# Soldering_Tip.net
KiCad netlist of a schematic drawn in Altium Designer
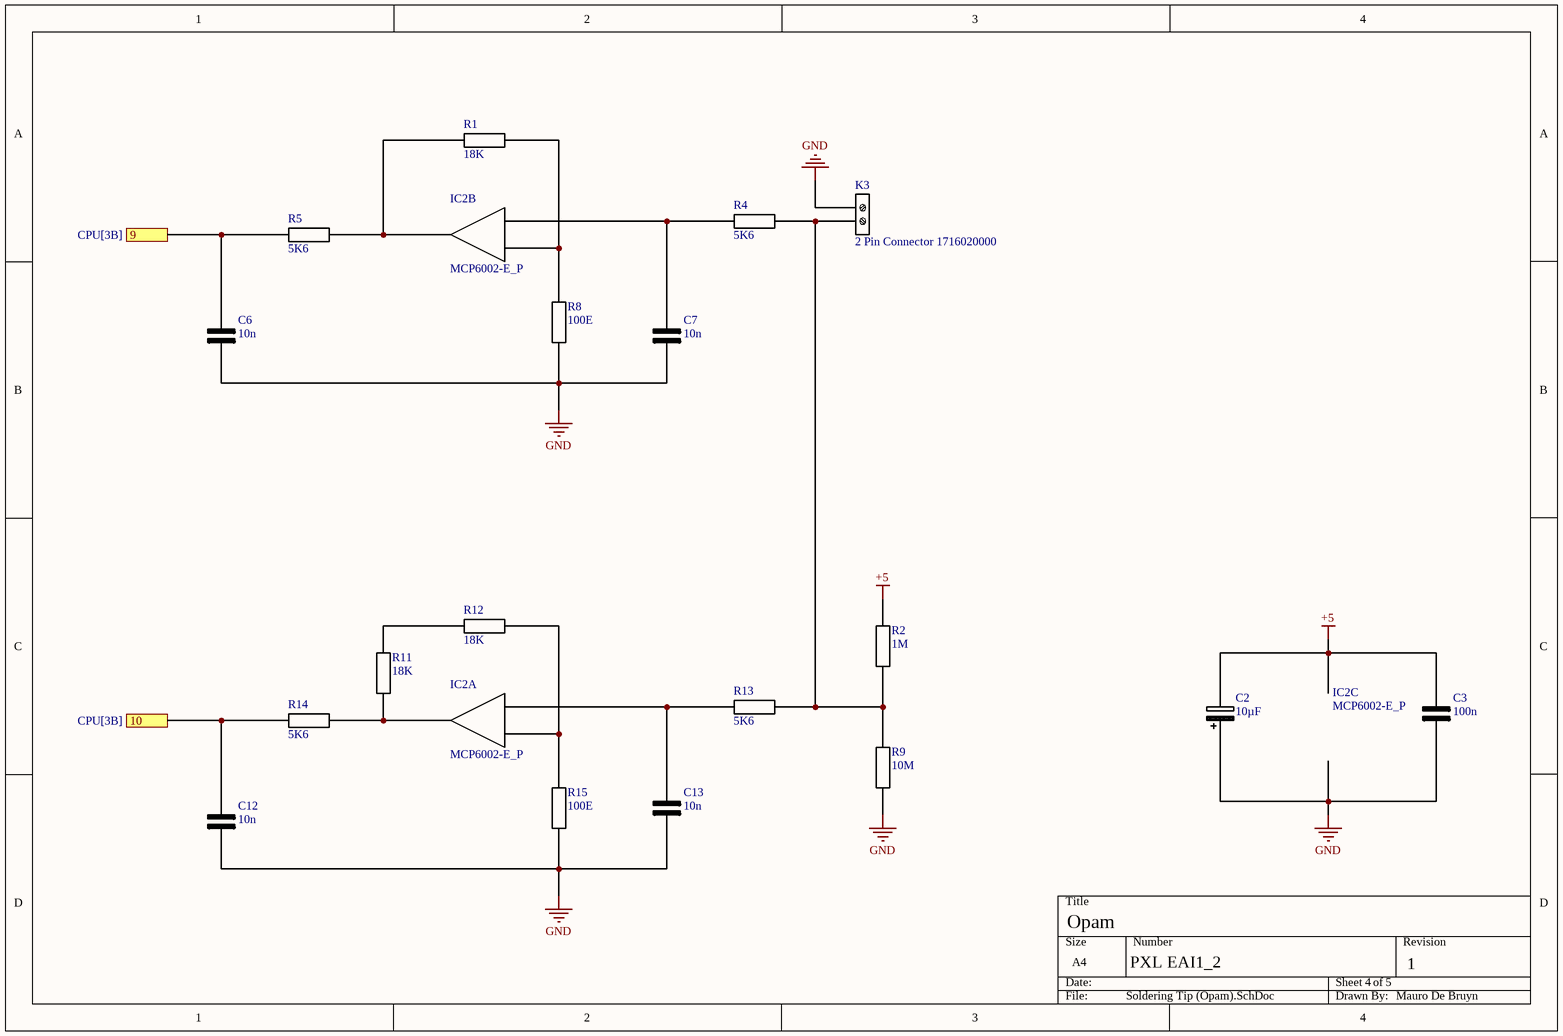
[diagram p0: Soldering Tip (Opam).SchDoc]

(export (version "E")
  (design (tool "Eeschema 10.0.6"))
  (components
    (comp (ref "C2")
      (value "10µF")
      (footprint "SamacSys:CAPPRD200W52D500H1250")
      (description "Capacitor Polarised")
      (fields
        (field (name "MOUSER2 PART NUMBER") "710-860020672010")
        (field (name "MANUFACTURER_PART_NUMBER") "860020672010")
      )
      (libsource (lib "SamacSys") (part "860020672010"))
    )
    (comp (ref "C3")
      (value "100n")
      (footprint "0805")
      (description "Capacitor")
      (fields (field (name "MANUFACTURER_PART_NUMBER") "C0805C391G3GACTU"))
      (libsource (lib "SamacSys") (part "0805 (Capacitor)"))
    )
    (comp (ref "C6")
      (value "10n")
      (footprint "0805")
      (description "Capacitor")
      (fields (field (name "MANUFACTURER_PART_NUMBER") "C0805C391G3GACTU"))
      (libsource (lib "SamacSys") (part "0805 (Capacitor)"))
    )
    (comp (ref "C7")
      (value "10n")
      (footprint "0805")
      (description "Capacitor")
      (fields (field (name "MANUFACTURER_PART_NUMBER") "C0805C391G3GACTU"))
      (libsource (lib "SamacSys") (part "0805 (Capacitor)"))
    )
    (comp (ref "C12")
      (value "10n")
      (footprint "0805")
      (description "Capacitor")
      (fields (field (name "MANUFACTURER_PART_NUMBER") "C0805C391G3GACTU"))
      (libsource (lib "SamacSys") (part "0805 (Capacitor)"))
    )
    (comp (ref "C13")
      (value "10n")
      (footprint "0805")
      (description "Capacitor")
      (fields (field (name "MANUFACTURER_PART_NUMBER") "C0805C391G3GACTU"))
      (libsource (lib "SamacSys") (part "0805 (Capacitor)"))
    )
    (comp (ref "IC2")
      (value "MCP6002-E_P")
      (footprint "SamacSys:DIP781W56P254L950H533Q8N")
      (description "Integrated Circuit")
      (fields
        (field (name "MOUSER2 PART NUMBER") "579-MCP6002-E/P")
        (field (name "MANUFACTURER_PART_NUMBER") "MCP6002-E/P")
      )
      (libsource (lib "SamacSys") (part "MCP6002-E_P"))
    )
    (comp (ref "K3")
      (value "2 Pin Connector 1716020000")
      (footprint "SamacSys:1716020000")
      (description "Connector")
      (fields (field (name "MANUFACTURER_PART_NUMBER") "1716020000"))
      (libsource (lib "SamacSys") (part "2 Pin Connector 1716020000"))
    )
    (comp (ref "R1")
      (value "18K")
      (footprint "0805")
      (description "Resistor")
      (fields (field (name "MANUFACTURER_PART_NUMBER") "C0805C391G3GACTU"))
      (libsource (lib "SamacSys") (part "0805 (Resistor)"))
    )
    (comp (ref "R2")
      (value "1M")
      (footprint "0805")
      (description "Resistor")
      (fields (field (name "MANUFACTURER_PART_NUMBER") "C0805C391G3GACTU"))
      (libsource (lib "SamacSys") (part "0805 (Resistor)"))
    )
    (comp (ref "R4")
      (value "5K6")
      (footprint "0805")
      (description "Resistor")
      (fields (field (name "MANUFACTURER_PART_NUMBER") "C0805C391G3GACTU"))
      (libsource (lib "SamacSys") (part "0805 (Resistor)"))
    )
    (comp (ref "R5")
      (value "5K6")
      (footprint "0805")
      (description "Resistor")
      (fields (field (name "MANUFACTURER_PART_NUMBER") "C0805C391G3GACTU"))
      (libsource (lib "SamacSys") (part "0805 (Resistor)"))
    )
    (comp (ref "R8")
      (value "100E")
      (footprint "0805")
      (description "Resistor")
      (fields (field (name "MANUFACTURER_PART_NUMBER") "C0805C391G3GACTU"))
      (libsource (lib "SamacSys") (part "0805 (Resistor)"))
    )
    (comp (ref "R9")
      (value "10M")
      (footprint "0805")
      (description "Resistor")
      (fields (field (name "MANUFACTURER_PART_NUMBER") "C0805C391G3GACTU"))
      (libsource (lib "SamacSys") (part "0805 (Resistor)"))
    )
    (comp (ref "R11")
      (value "18K")
      (footprint "0805")
      (description "Resistor")
      (fields (field (name "MANUFACTURER_PART_NUMBER") "C0805C391G3GACTU"))
      (libsource (lib "SamacSys") (part "0805 (Resistor)"))
    )
    (comp (ref "R12")
      (value "18K")
      (footprint "0805")
      (description "Resistor")
      (fields (field (name "MANUFACTURER_PART_NUMBER") "C0805C391G3GACTU"))
      (libsource (lib "SamacSys") (part "0805 (Resistor)"))
    )
    (comp (ref "R13")
      (value "5K6")
      (footprint "0805")
      (description "Resistor")
      (fields (field (name "MANUFACTURER_PART_NUMBER") "C0805C391G3GACTU"))
      (libsource (lib "SamacSys") (part "0805 (Resistor)"))
    )
    (comp (ref "R14")
      (value "5K6")
      (footprint "0805")
      (description "Resistor")
      (fields (field (name "MANUFACTURER_PART_NUMBER") "C0805C391G3GACTU"))
      (libsource (lib "SamacSys") (part "0805 (Resistor)"))
    )
    (comp (ref "R15")
      (value "100E")
      (footprint "0805")
      (description "Resistor")
      (fields (field (name "MANUFACTURER_PART_NUMBER") "C0805C391G3GACTU"))
      (libsource (lib "SamacSys") (part "0805 (Resistor)"))
    )
  )
  (nets
    (net (code "1") (name "+5") (class "Default")
      (node (ref "C2") (pin "2") (pinfunction "-_2") (pintype "passive"))
      (node (ref "C3") (pin "2") (pinfunction "-_2") (pintype "passive"))
      (node (ref "IC2") (pin "8") (pinfunction "VDD_8") (pintype "passive"))
      (node (ref "R2") (pin "2") (pinfunction "2_2") (pintype "passive"))
    )
    (net (code "2") (name "/9") (class "Default")
      (node (ref "C6") (pin "2") (pinfunction "-_2") (pintype "passive"))
      (node (ref "R5") (pin "1") (pinfunction "1_1") (pintype "passive"))
    )
    (net (code "3") (name "/10") (class "Default")
      (node (ref "C12") (pin "2") (pinfunction "-_2") (pintype "passive"))
      (node (ref "R14") (pin "1") (pinfunction "1_1") (pintype "passive"))
    )
    (net (code "4") (name "GND") (class "Default")
      (node (ref "C12") (pin "1") (pinfunction "+_1") (pintype "passive"))
      (node (ref "C13") (pin "1") (pinfunction "+_1") (pintype "passive"))
      (node (ref "C2") (pin "1") (pinfunction "+_1") (pintype "passive"))
      (node (ref "C3") (pin "1") (pinfunction "+_1") (pintype "passive"))
      (node (ref "C6") (pin "1") (pinfunction "+_1") (pintype "passive"))
      (node (ref "C7") (pin "1") (pinfunction "+_1") (pintype "passive"))
      (node (ref "IC2") (pin "4") (pinfunction "VSS_4") (pintype "passive"))
      (node (ref "K3") (pin "1") (pinfunction "1_1") (pintype "passive"))
      (node (ref "R15") (pin "1") (pinfunction "1_1") (pintype "passive"))
      (node (ref "R8") (pin "1") (pinfunction "1_1") (pintype "passive"))
      (node (ref "R9") (pin "1") (pinfunction "1_1") (pintype "passive"))
    )
    (net (code "5") (name "Net-(C7--)") (class "Default")
      (node (ref "C7") (pin "2") (pinfunction "-_2") (pintype "passive"))
      (node (ref "IC2") (pin "5") (pinfunction "VINB+_5") (pintype "passive"))
      (node (ref "R4") (pin "1") (pinfunction "1_1") (pintype "passive"))
    )
    (net (code "6") (name "Net-(C13--)") (class "Default")
      (node (ref "C13") (pin "2") (pinfunction "-_2") (pintype "passive"))
      (node (ref "IC2") (pin "3") (pinfunction "VINA+_3") (pintype "passive"))
      (node (ref "R13") (pin "1") (pinfunction "1_1") (pintype "passive"))
    )
    (net (code "7") (name "Net-(IC2A-VINA-)") (class "Default")
      (node (ref "IC2") (pin "2") (pinfunction "VINA-_2") (pintype "passive"))
      (node (ref "R12") (pin "1") (pinfunction "1_1") (pintype "passive"))
      (node (ref "R15") (pin "2") (pinfunction "2_2") (pintype "passive"))
    )
    (net (code "8") (name "Net-(IC2A-VOUTA)") (class "Default")
      (node (ref "IC2") (pin "1") (pinfunction "VOUTA_1") (pintype "passive"))
      (node (ref "R11") (pin "1") (pinfunction "1_1") (pintype "passive"))
      (node (ref "R14") (pin "2") (pinfunction "2_2") (pintype "passive"))
    )
    (net (code "9") (name "Net-(IC2B-VINB-)") (class "Default")
      (node (ref "IC2") (pin "6") (pinfunction "VINB-_6") (pintype "passive"))
      (node (ref "R1") (pin "2") (pinfunction "2_2") (pintype "passive"))
      (node (ref "R8") (pin "2") (pinfunction "2_2") (pintype "passive"))
    )
    (net (code "10") (name "Net-(IC2B-VOUTB)") (class "Default")
      (node (ref "IC2") (pin "7") (pinfunction "VOUTB_7") (pintype "passive"))
      (node (ref "R1") (pin "1") (pinfunction "1_1") (pintype "passive"))
      (node (ref "R5") (pin "2") (pinfunction "2_2") (pintype "passive"))
    )
    (net (code "11") (name "Net-(K3-Pad2)") (class "Default")
      (node (ref "K3") (pin "2") (pinfunction "2_2") (pintype "passive"))
      (node (ref "R13") (pin "2") (pinfunction "2_2") (pintype "passive"))
      (node (ref "R2") (pin "1") (pinfunction "1_1") (pintype "passive"))
      (node (ref "R4") (pin "2") (pinfunction "2_2") (pintype "passive"))
      (node (ref "R9") (pin "2") (pinfunction "2_2") (pintype "passive"))
    )
    (net (code "12") (name "Net-(R11-Pad2)") (class "Default")
      (node (ref "R11") (pin "2") (pinfunction "2_2") (pintype "passive"))
      (node (ref "R12") (pin "2") (pinfunction "2_2") (pintype "passive"))
    )
  )
)
